# Sch_Control.net
KiCad netlist of a schematic drawn in Altium Designer
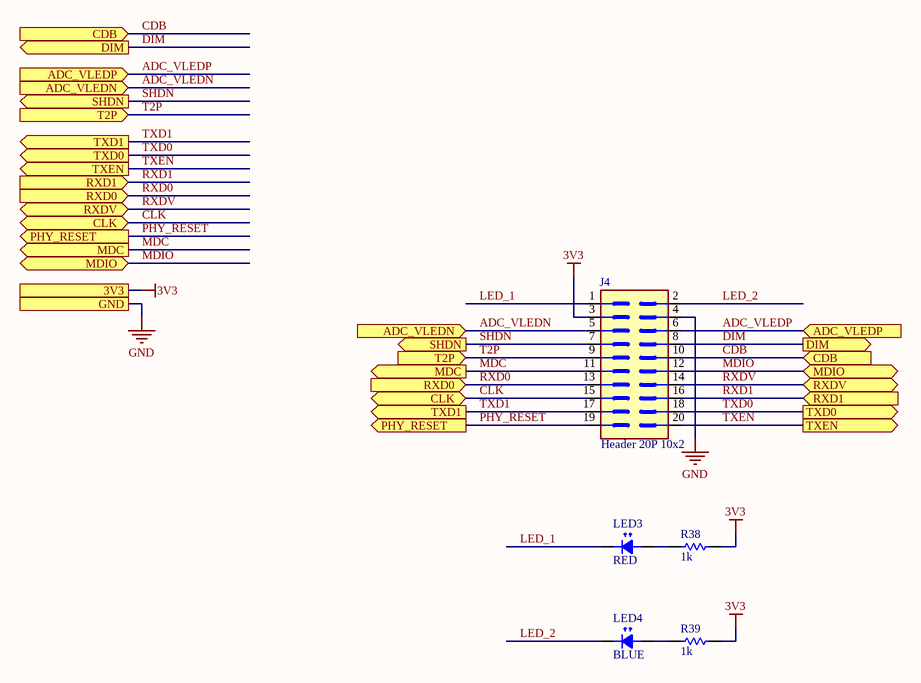
[diagram p0: Sch_Control.SchDoc]

(export (version "E")
  (design (tool "Eeschema 10.0.6"))
  (components
    (comp (ref "J4")
      (value "Header 20P 10x2")
      (footprint "CON_PTH_20P_HEADER_10x2_2.54mm_FEMALE")
      (description "10x2 20P PTH pin header - Generic")
      (libsource (lib "AltiumLibrary") (part "CON_PTH_HEADER_20P_10x2"))
    )
    (comp (ref "LED3")
      (value "RED")
      (footprint "LED_SMD_0603")
      (description "LED SMD - Generic")
      (libsource (lib "AltiumLibrary") (part "LED_SMD"))
    )
    (comp (ref "LED4")
      (value "BLUE")
      (footprint "LED_SMD_0603")
      (description "LED SMD - Generic")
      (libsource (lib "AltiumLibrary") (part "LED_SMD"))
    )
    (comp (ref "R38")
      (value "1k")
      (footprint "RES_SMD_0603")
      (description "Resistor SMD - Generic")
      (libsource (lib "AltiumLibrary") (part "RES_SMD"))
    )
    (comp (ref "R39")
      (value "1k")
      (footprint "RES_SMD_0603")
      (description "Resistor SMD - Generic")
      (libsource (lib "AltiumLibrary") (part "RES_SMD"))
    )
  )
  (nets
    (net (code "1") (name "/ADC_VLEDN") (class "Default")
      (node (ref "J4") (pin "5") (pinfunction "5_5") (pintype "passive"))
    )
    (net (code "2") (name "/ADC_VLEDP") (class "Default")
      (node (ref "J4") (pin "6") (pinfunction "6_6") (pintype "passive"))
    )
    (net (code "3") (name "/CDB") (class "Default")
      (node (ref "J4") (pin "10") (pinfunction "10_10") (pintype "passive"))
    )
    (net (code "4") (name "/CLK") (class "Default")
      (node (ref "J4") (pin "15") (pinfunction "15_15") (pintype "passive"))
    )
    (net (code "5") (name "/DIM") (class "Default")
      (node (ref "J4") (pin "8") (pinfunction "8_8") (pintype "passive"))
    )
    (net (code "6") (name "/LED_1") (class "Default")
      (node (ref "J4") (pin "1") (pinfunction "1_1") (pintype "passive"))
      (node (ref "LED3") (pin "K") (pinfunction "K_K") (pintype "passive"))
    )
    (net (code "7") (name "/LED_2") (class "Default")
      (node (ref "J4") (pin "2") (pinfunction "2_2") (pintype "passive"))
      (node (ref "LED4") (pin "K") (pinfunction "K_K") (pintype "passive"))
    )
    (net (code "8") (name "/MDC") (class "Default")
      (node (ref "J4") (pin "11") (pinfunction "11_11") (pintype "passive"))
    )
    (net (code "9") (name "/MDIO") (class "Default")
      (node (ref "J4") (pin "12") (pinfunction "12_12") (pintype "passive"))
    )
    (net (code "10") (name "/PHY_RESET") (class "Default")
      (node (ref "J4") (pin "19") (pinfunction "19_19") (pintype "passive"))
    )
    (net (code "11") (name "/RXD0") (class "Default")
      (node (ref "J4") (pin "13") (pinfunction "13_13") (pintype "passive"))
    )
    (net (code "12") (name "/RXD1") (class "Default")
      (node (ref "J4") (pin "16") (pinfunction "16_16") (pintype "passive"))
    )
    (net (code "13") (name "/RXDV") (class "Default")
      (node (ref "J4") (pin "14") (pinfunction "14_14") (pintype "passive"))
    )
    (net (code "14") (name "/SHDN") (class "Default")
      (node (ref "J4") (pin "7") (pinfunction "7_7") (pintype "passive"))
    )
    (net (code "15") (name "/T2P") (class "Default")
      (node (ref "J4") (pin "9") (pinfunction "9_9") (pintype "passive"))
    )
    (net (code "16") (name "/TXD0") (class "Default")
      (node (ref "J4") (pin "18") (pinfunction "18_18") (pintype "passive"))
    )
    (net (code "17") (name "/TXD1") (class "Default")
      (node (ref "J4") (pin "17") (pinfunction "17_17") (pintype "passive"))
    )
    (net (code "18") (name "/TXEN") (class "Default")
      (node (ref "J4") (pin "20") (pinfunction "20_20") (pintype "passive"))
    )
    (net (code "19") (name "3V3") (class "Default")
      (node (ref "J4") (pin "3") (pinfunction "3_3") (pintype "passive"))
      (node (ref "R38") (pin "1") (pinfunction "1_1") (pintype "passive"))
      (node (ref "R39") (pin "1") (pinfunction "1_1") (pintype "passive"))
    )
    (net (code "20") (name "GND") (class "Default")
      (node (ref "J4") (pin "4") (pinfunction "4_4") (pintype "passive"))
    )
    (net (code "21") (name "Net-(LED3-PadA)") (class "Default")
      (node (ref "LED3") (pin "A") (pinfunction "A_A") (pintype "passive"))
      (node (ref "R38") (pin "2") (pinfunction "2_2") (pintype "passive"))
    )
    (net (code "22") (name "Net-(LED4-PadA)") (class "Default")
      (node (ref "LED4") (pin "A") (pinfunction "A_A") (pintype "passive"))
      (node (ref "R39") (pin "2") (pinfunction "2_2") (pintype "passive"))
    )
  )
)
